# esp8266mb.net
KiCad netlist of a schematic drawn in EAGLE
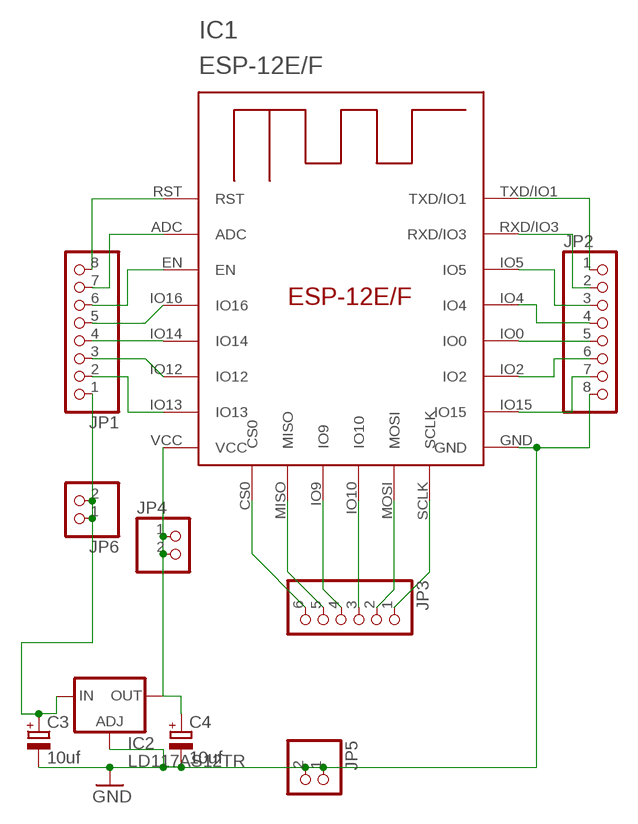
[diagram p0: schematic, sheet 1]

(export (version "E")
  (design (tool "Eeschema 10.0.6"))
  (components
    (comp (ref "C3")
      (value "10uf")
      (footprint "eagle-import:E5-5")
      (libsource (lib "eagle-import") (part "CPOL-EUE5-5"))
    )
    (comp (ref "C4")
      (value "10uf")
      (footprint "eagle-import:E5-5")
      (libsource (lib "eagle-import") (part "CPOL-EUE5-5"))
    )
    (comp (ref "IC1")
      (value "ESP-12E/F")
      (footprint "eagle-import:ESP-12E")
      (libsource (lib "eagle-import") (part "ESP-12E/F"))
    )
    (comp (ref "IC2")
      (value "LD117AS12TR")
      (footprint "eagle-import:SOT223")
      (libsource (lib "eagle-import") (part "LD117A?S12TR"))
    )
    (comp (ref "JP1")
      (value "PINHD-1X8")
      (footprint "eagle-import:1X08")
      (libsource (lib "eagle-import") (part "PINHD-1X8"))
    )
    (comp (ref "JP2")
      (value "PINHD-1X8")
      (footprint "eagle-import:1X08")
      (libsource (lib "eagle-import") (part "PINHD-1X8"))
    )
    (comp (ref "JP3")
      (value "PINHD-1X6")
      (footprint "eagle-import:1X06")
      (libsource (lib "eagle-import") (part "PINHD-1X6"))
    )
    (comp (ref "JP4")
      (value "PINHD-1X2")
      (footprint "eagle-import:1X02")
      (libsource (lib "eagle-import") (part "PINHD-1X2"))
    )
    (comp (ref "JP5")
      (value "PINHD-1X2")
      (footprint "eagle-import:1X02")
      (libsource (lib "eagle-import") (part "PINHD-1X2"))
    )
    (comp (ref "JP6")
      (value "PINHD-1X2")
      (footprint "eagle-import:1X02")
      (libsource (lib "eagle-import") (part "PINHD-1X2"))
    )
  )
  (nets
    (net (code "1") (name "GND") (class "Default")
      (node (ref "C3") (pin "-") (pinfunction "-_-") (pintype "passive"))
      (node (ref "C4") (pin "-") (pinfunction "-_-") (pintype "passive"))
      (node (ref "IC1") (pin "GND") (pinfunction "GND_GND") (pintype "power_in"))
      (node (ref "IC2") (pin "1") (pinfunction "ADJ_1") (pintype "input"))
      (node (ref "JP2") (pin "8") (pinfunction "8_8") (pintype "passive"))
      (node (ref "JP5") (pin "1") (pinfunction "1_1") (pintype "passive"))
      (node (ref "JP5") (pin "2") (pinfunction "2_2") (pintype "passive"))
    )
    (net (code "2") (name "Net-(IC1-PadADC)") (class "Default")
      (node (ref "IC1") (pin "ADC") (pinfunction "ADC_ADC") (pintype "bidirectional"))
      (node (ref "JP1") (pin "7") (pinfunction "7_7") (pintype "passive"))
    )
    (net (code "3") (name "Net-(IC1-PadCS0)") (class "Default")
      (node (ref "IC1") (pin "CS0") (pinfunction "CS0_CS0") (pintype "bidirectional"))
      (node (ref "JP3") (pin "6") (pinfunction "6_6") (pintype "passive"))
    )
    (net (code "4") (name "Net-(IC1-PadEN)") (class "Default")
      (node (ref "IC1") (pin "EN") (pinfunction "EN_EN") (pintype "bidirectional"))
      (node (ref "JP1") (pin "6") (pinfunction "6_6") (pintype "passive"))
    )
    (net (code "5") (name "Net-(IC1-PadIO0)") (class "Default")
      (node (ref "IC1") (pin "IO0") (pinfunction "IO0_IO0") (pintype "bidirectional"))
      (node (ref "JP2") (pin "5") (pinfunction "5_5") (pintype "passive"))
    )
    (net (code "6") (name "Net-(IC1-PadIO2)") (class "Default")
      (node (ref "IC1") (pin "IO2") (pinfunction "IO2_IO2") (pintype "bidirectional"))
      (node (ref "JP2") (pin "6") (pinfunction "6_6") (pintype "passive"))
    )
    (net (code "7") (name "Net-(IC1-PadIO4)") (class "Default")
      (node (ref "IC1") (pin "IO4") (pinfunction "IO4_IO4") (pintype "bidirectional"))
      (node (ref "JP2") (pin "4") (pinfunction "4_4") (pintype "passive"))
    )
    (net (code "8") (name "Net-(IC1-PadIO5)") (class "Default")
      (node (ref "IC1") (pin "IO5") (pinfunction "IO5_IO5") (pintype "bidirectional"))
      (node (ref "JP2") (pin "3") (pinfunction "3_3") (pintype "passive"))
    )
    (net (code "9") (name "Net-(IC1-PadIO9)") (class "Default")
      (node (ref "IC1") (pin "IO9") (pinfunction "IO9_IO9") (pintype "bidirectional"))
      (node (ref "JP3") (pin "4") (pinfunction "4_4") (pintype "passive"))
    )
    (net (code "10") (name "Net-(IC1-PadIO10)") (class "Default")
      (node (ref "IC1") (pin "IO10") (pinfunction "IO10_IO10") (pintype "bidirectional"))
      (node (ref "JP3") (pin "3") (pinfunction "3_3") (pintype "passive"))
    )
    (net (code "11") (name "Net-(IC1-PadIO12)") (class "Default")
      (node (ref "IC1") (pin "IO12") (pinfunction "IO12_IO12") (pintype "bidirectional"))
      (node (ref "JP1") (pin "3") (pinfunction "3_3") (pintype "passive"))
    )
    (net (code "12") (name "Net-(IC1-PadIO13)") (class "Default")
      (node (ref "IC1") (pin "IO13") (pinfunction "IO13_IO13") (pintype "bidirectional"))
      (node (ref "JP1") (pin "2") (pinfunction "2_2") (pintype "passive"))
    )
    (net (code "13") (name "Net-(IC1-PadIO14)") (class "Default")
      (node (ref "IC1") (pin "IO14") (pinfunction "IO14_IO14") (pintype "bidirectional"))
      (node (ref "JP1") (pin "4") (pinfunction "4_4") (pintype "passive"))
    )
    (net (code "14") (name "Net-(IC1-PadIO15)") (class "Default")
      (node (ref "IC1") (pin "IO15") (pinfunction "IO15_IO15") (pintype "bidirectional"))
      (node (ref "JP2") (pin "7") (pinfunction "7_7") (pintype "passive"))
    )
    (net (code "15") (name "Net-(IC1-PadIO16)") (class "Default")
      (node (ref "IC1") (pin "IO16") (pinfunction "IO16_IO16") (pintype "bidirectional"))
      (node (ref "JP1") (pin "5") (pinfunction "5_5") (pintype "passive"))
    )
    (net (code "16") (name "Net-(IC1-PadMISO)") (class "Default")
      (node (ref "IC1") (pin "MISO") (pinfunction "MISO_MISO") (pintype "bidirectional"))
      (node (ref "JP3") (pin "5") (pinfunction "5_5") (pintype "passive"))
    )
    (net (code "17") (name "Net-(IC1-PadMOSI)") (class "Default")
      (node (ref "IC1") (pin "MOSI") (pinfunction "MOSI_MOSI") (pintype "bidirectional"))
      (node (ref "JP3") (pin "2") (pinfunction "2_2") (pintype "passive"))
    )
    (net (code "18") (name "Net-(IC1-PadRST)") (class "Default")
      (node (ref "IC1") (pin "RST") (pinfunction "RST_RST") (pintype "input"))
      (node (ref "JP1") (pin "8") (pinfunction "8_8") (pintype "passive"))
    )
    (net (code "19") (name "Net-(IC1-PadRXD{slash}IO3)") (class "Default")
      (node (ref "IC1") (pin "RXD/IO3") (pinfunction "RXD/IO3_RXD/IO3") (pintype "bidirectional"))
      (node (ref "JP2") (pin "2") (pinfunction "2_2") (pintype "passive"))
    )
    (net (code "20") (name "Net-(IC1-PadSCLK)") (class "Default")
      (node (ref "IC1") (pin "SCLK") (pinfunction "SCLK_SCLK") (pintype "bidirectional"))
      (node (ref "JP3") (pin "1") (pinfunction "1_1") (pintype "passive"))
    )
    (net (code "21") (name "Net-(IC1-PadTXD{slash}IO1)") (class "Default")
      (node (ref "IC1") (pin "TXD/IO1") (pinfunction "TXD/IO1_TXD/IO1") (pintype "bidirectional"))
      (node (ref "JP2") (pin "1") (pinfunction "1_1") (pintype "passive"))
    )
    (net (code "22") (name "Net-(IC2-IN)") (class "Default")
      (node (ref "C3") (pin "+") (pinfunction "+_+") (pintype "passive"))
      (node (ref "IC2") (pin "3") (pinfunction "IN_3") (pintype "input"))
      (node (ref "JP1") (pin "1") (pinfunction "1_1") (pintype "passive"))
      (node (ref "JP6") (pin "1") (pinfunction "1_1") (pintype "passive"))
      (node (ref "JP6") (pin "2") (pinfunction "2_2") (pintype "passive"))
    )
    (net (code "23") (name "Net-(IC2-OUT)") (class "Default")
      (node (ref "C4") (pin "+") (pinfunction "+_+") (pintype "passive"))
      (node (ref "IC1") (pin "VCC") (pinfunction "VCC_VCC") (pintype "power_in"))
      (node (ref "IC2") (pin "4") (pinfunction "OUT_4") (pintype "passive"))
      (node (ref "JP4") (pin "1") (pinfunction "1_1") (pintype "passive"))
      (node (ref "JP4") (pin "2") (pinfunction "2_2") (pintype "passive"))
    )
  )
)
